# feuchtigkeitssensor-wasserpumpe-arduino-.net
KiCad netlist of a schematic drawn in EAGLE
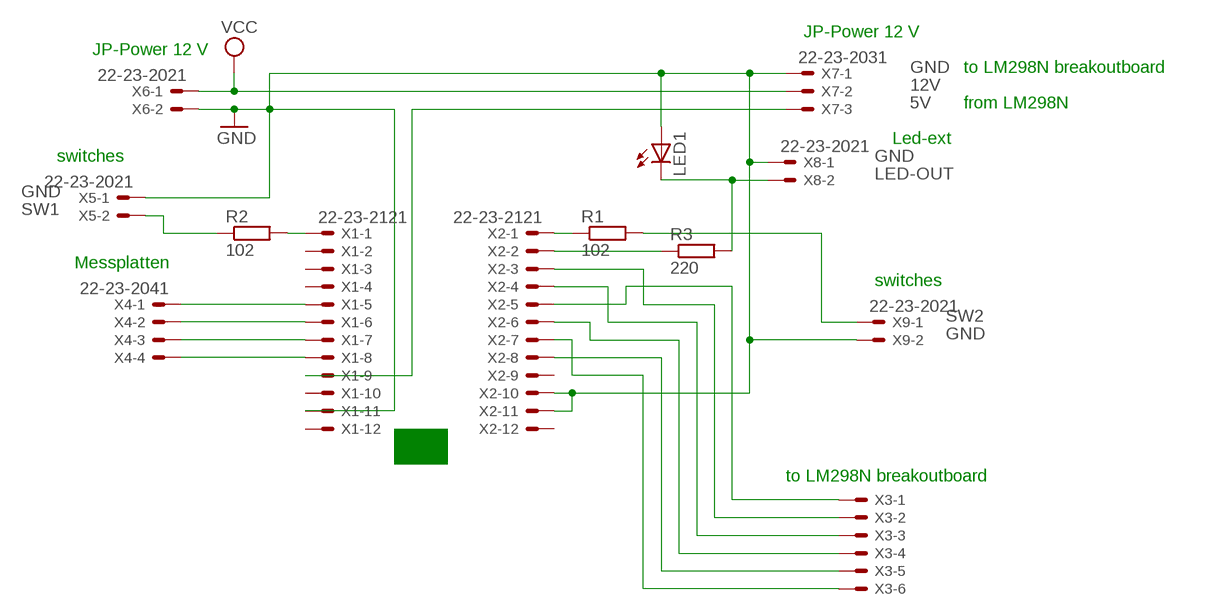
[diagram p0: schematic, sheet 1]

(export (version "E")
  (design (tool "Eeschema 10.0.6"))
  (components
    (comp (ref "LED1")
      (value "LED5MM")
      (footprint "eagle-import:LED5MM")
      (libsource (lib "eagle-import") (part "LED5MM"))
    )
    (comp (ref "R1")
      (value "102")
      (footprint "eagle-import:M1206")
      (libsource (lib "eagle-import") (part "R-EU_M1206"))
    )
    (comp (ref "R2")
      (value "102")
      (footprint "eagle-import:M1206")
      (libsource (lib "eagle-import") (part "R-EU_M1206"))
    )
    (comp (ref "R3")
      (value "220")
      (footprint "eagle-import:M1206")
      (libsource (lib "eagle-import") (part "R-EU_M1206"))
    )
    (comp (ref "X1")
      (value "22-23-2121")
      (footprint "eagle-import:22-23-2121")
      (fields (field (name "MF") "MOLEX"))
      (libsource (lib "eagle-import") (part "22-23-2121"))
    )
    (comp (ref "X2")
      (value "22-23-2121")
      (footprint "eagle-import:22-23-2121")
      (fields (field (name "MF") "MOLEX"))
      (libsource (lib "eagle-import") (part "22-23-2121"))
    )
    (comp (ref "X3")
      (value "22-23-2061")
      (footprint "eagle-import:22-23-2061")
      (fields (field (name "MF") "MOLEX"))
      (libsource (lib "eagle-import") (part "22-23-2061"))
    )
    (comp (ref "X4")
      (value "22-23-2041")
      (footprint "eagle-import:22-23-2041")
      (fields (field (name "MF") "MOLEX"))
      (libsource (lib "eagle-import") (part "22-23-2041"))
    )
    (comp (ref "X5")
      (value "22-23-2021")
      (footprint "eagle-import:22-23-2021")
      (fields (field (name "MF") "MOLEX"))
      (libsource (lib "eagle-import") (part "22-23-2021"))
    )
    (comp (ref "X6")
      (value "22-23-2021")
      (footprint "eagle-import:22-23-2021")
      (fields (field (name "MF") "MOLEX"))
      (libsource (lib "eagle-import") (part "22-23-2021"))
    )
    (comp (ref "X7")
      (value "22-23-2031")
      (footprint "eagle-import:22-23-2031")
      (fields (field (name "MF") "MOLEX"))
      (libsource (lib "eagle-import") (part "22-23-2031"))
    )
    (comp (ref "X8")
      (value "22-23-2021")
      (footprint "eagle-import:22-23-2021")
      (fields (field (name "MF") "MOLEX"))
      (libsource (lib "eagle-import") (part "22-23-2021"))
    )
    (comp (ref "X9")
      (value "22-23-2021")
      (footprint "eagle-import:22-23-2021")
      (fields (field (name "MF") "MOLEX"))
      (libsource (lib "eagle-import") (part "22-23-2021"))
    )
  )
  (nets
    (net (code "1") (name "/5V") (class "Default")
      (node (ref "X1") (pin "9") (pinfunction "S_9") (pintype "passive"))
      (node (ref "X7") (pin "3") (pinfunction "S_3") (pintype "passive"))
    )
    (net (code "2") (name "/LED-OUT") (class "Default")
      (node (ref "LED1") (pin "K") (pinfunction "C_K") (pintype "passive"))
      (node (ref "R3") (pin "2") (pinfunction "2_2") (pintype "passive"))
      (node (ref "X8") (pin "2") (pinfunction "S_2") (pintype "passive"))
    )
    (net (code "3") (name "/SW1") (class "Default")
      (node (ref "R2") (pin "1") (pinfunction "1_1") (pintype "passive"))
      (node (ref "X5") (pin "2") (pinfunction "S_2") (pintype "passive"))
    )
    (net (code "4") (name "/SW2") (class "Default")
      (node (ref "R1") (pin "2") (pinfunction "2_2") (pintype "passive"))
      (node (ref "X9") (pin "1") (pinfunction "S_1") (pintype "passive"))
    )
    (net (code "5") (name "GND") (class "Default")
      (node (ref "LED1") (pin "A") (pinfunction "A_A") (pintype "passive"))
      (node (ref "X1") (pin "11") (pinfunction "S_11") (pintype "passive"))
      (node (ref "X2") (pin "10") (pinfunction "S_10") (pintype "passive"))
      (node (ref "X2") (pin "11") (pinfunction "S_11") (pintype "passive"))
      (node (ref "X5") (pin "1") (pinfunction "S_1") (pintype "passive"))
      (node (ref "X6") (pin "2") (pinfunction "S_2") (pintype "passive"))
      (node (ref "X7") (pin "1") (pinfunction "S_1") (pintype "passive"))
      (node (ref "X8") (pin "1") (pinfunction "S_1") (pintype "passive"))
      (node (ref "X9") (pin "2") (pinfunction "S_2") (pintype "passive"))
    )
    (net (code "6") (name "Net-(X1A-S)") (class "Default")
      (node (ref "R2") (pin "2") (pinfunction "2_2") (pintype "passive"))
      (node (ref "X1") (pin "1") (pinfunction "S_1") (pintype "passive"))
    )
    (net (code "7") (name "Net-(X1H-S)") (class "Default")
      (node (ref "X1") (pin "5") (pinfunction "S_5") (pintype "passive"))
      (node (ref "X4") (pin "1") (pinfunction "S_1") (pintype "passive"))
    )
    (net (code "8") (name "Net-(X1I-S)") (class "Default")
      (node (ref "X1") (pin "6") (pinfunction "S_6") (pintype "passive"))
      (node (ref "X4") (pin "2") (pinfunction "S_2") (pintype "passive"))
    )
    (net (code "9") (name "Net-(X1J-S)") (class "Default")
      (node (ref "X1") (pin "7") (pinfunction "S_7") (pintype "passive"))
      (node (ref "X4") (pin "3") (pinfunction "S_3") (pintype "passive"))
    )
    (net (code "10") (name "Net-(X1K-S)") (class "Default")
      (node (ref "X1") (pin "8") (pinfunction "S_8") (pintype "passive"))
      (node (ref "X4") (pin "4") (pinfunction "S_4") (pintype "passive"))
    )
    (net (code "11") (name "Net-(X2A-S)") (class "Default")
      (node (ref "R1") (pin "1") (pinfunction "1_1") (pintype "passive"))
      (node (ref "X2") (pin "1") (pinfunction "S_1") (pintype "passive"))
    )
    (net (code "12") (name "Net-(X2E-S)") (class "Default")
      (node (ref "R3") (pin "1") (pinfunction "1_1") (pintype "passive"))
      (node (ref "X2") (pin "2") (pinfunction "S_2") (pintype "passive"))
    )
    (net (code "13") (name "Net-(X2F-S)") (class "Default")
      (node (ref "X2") (pin "3") (pinfunction "S_3") (pintype "passive"))
      (node (ref "X3") (pin "2") (pinfunction "S_2") (pintype "passive"))
    )
    (net (code "14") (name "Net-(X2G-S)") (class "Default")
      (node (ref "X2") (pin "4") (pinfunction "S_4") (pintype "passive"))
      (node (ref "X3") (pin "3") (pinfunction "S_3") (pintype "passive"))
    )
    (net (code "15") (name "Net-(X2H-S)") (class "Default")
      (node (ref "X2") (pin "5") (pinfunction "S_5") (pintype "passive"))
      (node (ref "X3") (pin "1") (pinfunction "S_1") (pintype "passive"))
    )
    (net (code "16") (name "Net-(X2I-S)") (class "Default")
      (node (ref "X2") (pin "6") (pinfunction "S_6") (pintype "passive"))
      (node (ref "X3") (pin "4") (pinfunction "S_4") (pintype "passive"))
    )
    (net (code "17") (name "Net-(X2J-S)") (class "Default")
      (node (ref "X2") (pin "7") (pinfunction "S_7") (pintype "passive"))
      (node (ref "X3") (pin "6") (pinfunction "S_6") (pintype "passive"))
    )
    (net (code "18") (name "Net-(X2K-S)") (class "Default")
      (node (ref "X2") (pin "8") (pinfunction "S_8") (pintype "passive"))
      (node (ref "X3") (pin "5") (pinfunction "S_5") (pintype "passive"))
    )
    (net (code "19") (name "VCC") (class "Default")
      (node (ref "X6") (pin "1") (pinfunction "S_1") (pintype "passive"))
      (node (ref "X7") (pin "2") (pinfunction "S_2") (pintype "passive"))
    )
    (net (code "20") (name "unconnected-(X1B-S-Pad10)") (class "Default")
      (node (ref "X1") (pin "10") (pinfunction "S_10") (pintype "passive"))
    )
    (net (code "21") (name "unconnected-(X1D-S-Pad12)") (class "Default")
      (node (ref "X1") (pin "12") (pinfunction "S_12") (pintype "passive"))
    )
    (net (code "22") (name "unconnected-(X1E-S-Pad2)") (class "Default")
      (node (ref "X1") (pin "2") (pinfunction "S_2") (pintype "passive"))
    )
    (net (code "23") (name "unconnected-(X1F-S-Pad3)") (class "Default")
      (node (ref "X1") (pin "3") (pinfunction "S_3") (pintype "passive"))
    )
    (net (code "24") (name "unconnected-(X1G-S-Pad4)") (class "Default")
      (node (ref "X1") (pin "4") (pinfunction "S_4") (pintype "passive"))
    )
    (net (code "25") (name "unconnected-(X2D-S-Pad12)") (class "Default")
      (node (ref "X2") (pin "12") (pinfunction "S_12") (pintype "passive"))
    )
    (net (code "26") (name "unconnected-(X2L-S-Pad9)") (class "Default")
      (node (ref "X2") (pin "9") (pinfunction "S_9") (pintype "passive"))
    )
  )
)
